# Top.net
KiCad netlist of a schematic drawn in Altium Designer
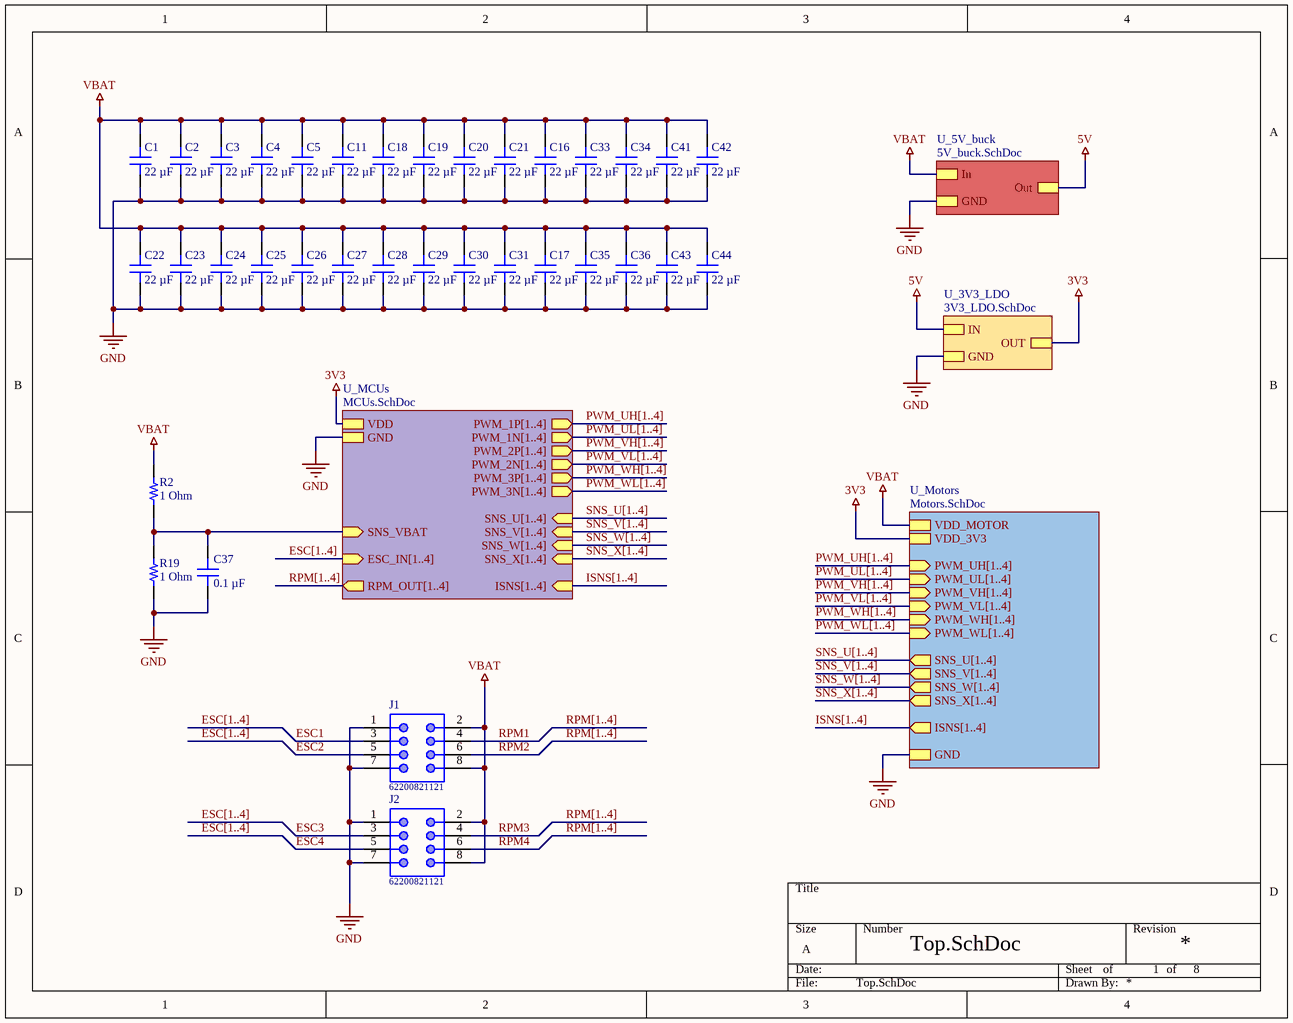
[diagram p0: Top.SchDoc]

(export (version "E")
  (design (tool "Eeschema 10.0.6"))
  (components
    (comp (ref "C1")
      (value "22 µF")
      (footprint "CAP 0805_2012")
      (description "CAP CER 22UF 25V X5R 0805")
      (fields (field (name "PART NUMBER") "CC0805MKX5R8BB226") (field (name "MANUFACTURER") "Yageo"))
      (libsource (lib "Celestial Altium Library - altium_library") (part "Capacitor"))
    )
    (comp (ref "C2")
      (value "22 µF")
      (footprint "CAP 0805_2012")
      (description "CAP CER 22UF 25V X5R 0805")
      (fields (field (name "PART NUMBER") "CC0805MKX5R8BB226") (field (name "MANUFACTURER") "Yageo"))
      (libsource (lib "Celestial Altium Library - altium_library") (part "Capacitor"))
    )
    (comp (ref "C3")
      (value "22 µF")
      (footprint "CAP 0805_2012")
      (description "CAP CER 22UF 25V X5R 0805")
      (fields (field (name "PART NUMBER") "CC0805MKX5R8BB226") (field (name "MANUFACTURER") "Yageo"))
      (libsource (lib "Celestial Altium Library - altium_library") (part "Capacitor"))
    )
    (comp (ref "C4")
      (value "22 µF")
      (footprint "CAP 0805_2012")
      (description "CAP CER 22UF 25V X5R 0805")
      (fields (field (name "PART NUMBER") "CC0805MKX5R8BB226") (field (name "MANUFACTURER") "Yageo"))
      (libsource (lib "Celestial Altium Library - altium_library") (part "Capacitor"))
    )
    (comp (ref "C5")
      (value "22 µF")
      (footprint "CAP 0805_2012")
      (description "CAP CER 22UF 25V X5R 0805")
      (fields (field (name "PART NUMBER") "CC0805MKX5R8BB226") (field (name "MANUFACTURER") "Yageo"))
      (libsource (lib "Celestial Altium Library - altium_library") (part "Capacitor"))
    )
    (comp (ref "C11")
      (value "22 µF")
      (footprint "CAP 0805_2012")
      (description "CAP CER 22UF 25V X5R 0805")
      (fields (field (name "PART NUMBER") "CC0805MKX5R8BB226") (field (name "MANUFACTURER") "Yageo"))
      (libsource (lib "Celestial Altium Library - altium_library") (part "Capacitor"))
    )
    (comp (ref "C16")
      (value "22 µF")
      (footprint "CAP 0805_2012")
      (description "CAP CER 22UF 25V X5R 0805")
      (fields (field (name "PART NUMBER") "CC0805MKX5R8BB226") (field (name "MANUFACTURER") "Yageo"))
      (libsource (lib "Celestial Altium Library - altium_library") (part "Capacitor"))
    )
    (comp (ref "C17")
      (value "22 µF")
      (footprint "CAP 0805_2012")
      (description "CAP CER 22UF 25V X5R 0805")
      (fields (field (name "PART NUMBER") "CC0805MKX5R8BB226") (field (name "MANUFACTURER") "Yageo"))
      (libsource (lib "Celestial Altium Library - altium_library") (part "Capacitor"))
    )
    (comp (ref "C18")
      (value "22 µF")
      (footprint "CAP 0805_2012")
      (description "CAP CER 22UF 25V X5R 0805")
      (fields (field (name "PART NUMBER") "CC0805MKX5R8BB226") (field (name "MANUFACTURER") "Yageo"))
      (libsource (lib "Celestial Altium Library - altium_library") (part "Capacitor"))
    )
    (comp (ref "C19")
      (value "22 µF")
      (footprint "CAP 0805_2012")
      (description "CAP CER 22UF 25V X5R 0805")
      (fields (field (name "PART NUMBER") "CC0805MKX5R8BB226") (field (name "MANUFACTURER") "Yageo"))
      (libsource (lib "Celestial Altium Library - altium_library") (part "Capacitor"))
    )
    (comp (ref "C20")
      (value "22 µF")
      (footprint "CAP 0805_2012")
      (description "CAP CER 22UF 25V X5R 0805")
      (fields (field (name "PART NUMBER") "CC0805MKX5R8BB226") (field (name "MANUFACTURER") "Yageo"))
      (libsource (lib "Celestial Altium Library - altium_library") (part "Capacitor"))
    )
    (comp (ref "C21")
      (value "22 µF")
      (footprint "CAP 0805_2012")
      (description "CAP CER 22UF 25V X5R 0805")
      (fields (field (name "PART NUMBER") "CC0805MKX5R8BB226") (field (name "MANUFACTURER") "Yageo"))
      (libsource (lib "Celestial Altium Library - altium_library") (part "Capacitor"))
    )
    (comp (ref "C22")
      (value "22 µF")
      (footprint "CAP 0805_2012")
      (description "CAP CER 22UF 25V X5R 0805")
      (fields (field (name "PART NUMBER") "CC0805MKX5R8BB226") (field (name "MANUFACTURER") "Yageo"))
      (libsource (lib "Celestial Altium Library - altium_library") (part "Capacitor"))
    )
    (comp (ref "C23")
      (value "22 µF")
      (footprint "CAP 0805_2012")
      (description "CAP CER 22UF 25V X5R 0805")
      (fields (field (name "PART NUMBER") "CC0805MKX5R8BB226") (field (name "MANUFACTURER") "Yageo"))
      (libsource (lib "Celestial Altium Library - altium_library") (part "Capacitor"))
    )
    (comp (ref "C24")
      (value "22 µF")
      (footprint "CAP 0805_2012")
      (description "CAP CER 22UF 25V X5R 0805")
      (fields (field (name "PART NUMBER") "CC0805MKX5R8BB226") (field (name "MANUFACTURER") "Yageo"))
      (libsource (lib "Celestial Altium Library - altium_library") (part "Capacitor"))
    )
    (comp (ref "C25")
      (value "22 µF")
      (footprint "CAP 0805_2012")
      (description "CAP CER 22UF 25V X5R 0805")
      (fields (field (name "PART NUMBER") "CC0805MKX5R8BB226") (field (name "MANUFACTURER") "Yageo"))
      (libsource (lib "Celestial Altium Library - altium_library") (part "Capacitor"))
    )
    (comp (ref "C26")
      (value "22 µF")
      (footprint "CAP 0805_2012")
      (description "CAP CER 22UF 25V X5R 0805")
      (fields (field (name "PART NUMBER") "CC0805MKX5R8BB226") (field (name "MANUFACTURER") "Yageo"))
      (libsource (lib "Celestial Altium Library - altium_library") (part "Capacitor"))
    )
    (comp (ref "C27")
      (value "22 µF")
      (footprint "CAP 0805_2012")
      (description "CAP CER 22UF 25V X5R 0805")
      (fields (field (name "PART NUMBER") "CC0805MKX5R8BB226") (field (name "MANUFACTURER") "Yageo"))
      (libsource (lib "Celestial Altium Library - altium_library") (part "Capacitor"))
    )
    (comp (ref "C28")
      (value "22 µF")
      (footprint "CAP 0805_2012")
      (description "CAP CER 22UF 25V X5R 0805")
      (fields (field (name "PART NUMBER") "CC0805MKX5R8BB226") (field (name "MANUFACTURER") "Yageo"))
      (libsource (lib "Celestial Altium Library - altium_library") (part "Capacitor"))
    )
    (comp (ref "C29")
      (value "22 µF")
      (footprint "CAP 0805_2012")
      (description "CAP CER 22UF 25V X5R 0805")
      (fields (field (name "PART NUMBER") "CC0805MKX5R8BB226") (field (name "MANUFACTURER") "Yageo"))
      (libsource (lib "Celestial Altium Library - altium_library") (part "Capacitor"))
    )
    (comp (ref "C30")
      (value "22 µF")
      (footprint "CAP 0805_2012")
      (description "CAP CER 22UF 25V X5R 0805")
      (fields (field (name "PART NUMBER") "CC0805MKX5R8BB226") (field (name "MANUFACTURER") "Yageo"))
      (libsource (lib "Celestial Altium Library - altium_library") (part "Capacitor"))
    )
    (comp (ref "C31")
      (value "22 µF")
      (footprint "CAP 0805_2012")
      (description "CAP CER 22UF 25V X5R 0805")
      (fields (field (name "PART NUMBER") "CC0805MKX5R8BB226") (field (name "MANUFACTURER") "Yageo"))
      (libsource (lib "Celestial Altium Library - altium_library") (part "Capacitor"))
    )
    (comp (ref "C33")
      (value "22 µF")
      (footprint "CAP 0805_2012")
      (description "CAP CER 22UF 25V X5R 0805")
      (fields (field (name "PART NUMBER") "CC0805MKX5R8BB226") (field (name "MANUFACTURER") "Yageo"))
      (libsource (lib "Celestial Altium Library - altium_library") (part "Capacitor"))
    )
    (comp (ref "C34")
      (value "22 µF")
      (footprint "CAP 0805_2012")
      (description "CAP CER 22UF 25V X5R 0805")
      (fields (field (name "PART NUMBER") "CC0805MKX5R8BB226") (field (name "MANUFACTURER") "Yageo"))
      (libsource (lib "Celestial Altium Library - altium_library") (part "Capacitor"))
    )
    (comp (ref "C35")
      (value "22 µF")
      (footprint "CAP 0805_2012")
      (description "CAP CER 22UF 25V X5R 0805")
      (fields (field (name "PART NUMBER") "CC0805MKX5R8BB226") (field (name "MANUFACTURER") "Yageo"))
      (libsource (lib "Celestial Altium Library - altium_library") (part "Capacitor"))
    )
    (comp (ref "C36")
      (value "22 µF")
      (footprint "CAP 0805_2012")
      (description "CAP CER 22UF 25V X5R 0805")
      (fields (field (name "PART NUMBER") "CC0805MKX5R8BB226") (field (name "MANUFACTURER") "Yageo"))
      (libsource (lib "Celestial Altium Library - altium_library") (part "Capacitor"))
    )
    (comp (ref "C37")
      (value "0.1 µF")
      (footprint "CAP 0402_1005")
      (description "CAP CER 0.1UF 16V X7R 0402")
      (fields (field (name "PART NUMBER") "C0402C104K4RACAUTO") (field (name "MANUFACTURER") "KEMET"))
      (libsource (lib "Celestial Altium Library - altium_library") (part "Capacitor"))
    )
    (comp (ref "C41")
      (value "22 µF")
      (footprint "CAP 0805_2012")
      (description "CAP CER 22UF 25V X5R 0805")
      (fields (field (name "PART NUMBER") "CC0805MKX5R8BB226") (field (name "MANUFACTURER") "Yageo"))
      (libsource (lib "Celestial Altium Library - altium_library") (part "Capacitor"))
    )
    (comp (ref "C42")
      (value "22 µF")
      (footprint "CAP 0805_2012")
      (description "CAP CER 22UF 25V X5R 0805")
      (fields (field (name "PART NUMBER") "CC0805MKX5R8BB226") (field (name "MANUFACTURER") "Yageo"))
      (libsource (lib "Celestial Altium Library - altium_library") (part "Capacitor"))
    )
    (comp (ref "C43")
      (value "22 µF")
      (footprint "CAP 0805_2012")
      (description "CAP CER 22UF 25V X5R 0805")
      (fields (field (name "PART NUMBER") "CC0805MKX5R8BB226") (field (name "MANUFACTURER") "Yageo"))
      (libsource (lib "Celestial Altium Library - altium_library") (part "Capacitor"))
    )
    (comp (ref "C44")
      (value "22 µF")
      (footprint "CAP 0805_2012")
      (description "CAP CER 22UF 25V X5R 0805")
      (fields (field (name "PART NUMBER") "CC0805MKX5R8BB226") (field (name "MANUFACTURER") "Yageo"))
      (libsource (lib "Celestial Altium Library - altium_library") (part "Capacitor"))
    )
    (comp (ref "J1")
      (value "62200821121")
      (footprint "62200821121")
      (description "WR-PHD Pin Header, THT, pitch 1.27mm, Dual Row, Vertical, 8p")
      (fields (field (name "MANUFACTURER") "Wurth Elektronik"))
      (libsource (lib "Altium_WR-PHD") (part "62200821121"))
    )
    (comp (ref "J2")
      (value "62200821121")
      (footprint "62200821121")
      (description "WR-PHD Pin Header, THT, pitch 1.27mm, Dual Row, Vertical, 8p")
      (fields (field (name "MANUFACTURER") "Wurth Elektronik"))
      (libsource (lib "Altium_WR-PHD") (part "62200821121"))
    )
    (comp (ref "R2")
      (value "1 Ohm")
      (footprint "RES 0402_1005")
      (description "RES 14.3K OHM 1% 1/10W 0402")
      (fields
        (field (name "PART NUMBER") "RK73H1ETTP1432F")
        (field (name "MANUFACTURER") "KOA Speer Electronics, Inc.")
      )
      (libsource (lib "Celestial Altium Library - altium_library") (part "Resistor"))
    )
    (comp (ref "R19")
      (value "1 Ohm")
      (footprint "RES 0402_1005")
      (description "RES 14.3K OHM 1% 1/10W 0402")
      (fields
        (field (name "PART NUMBER") "RK73H1ETTP1432F")
        (field (name "MANUFACTURER") "KOA Speer Electronics, Inc.")
      )
      (libsource (lib "Celestial Altium Library - altium_library") (part "Resistor"))
    )
  )
  (nets
    (net (code "45") (name "/ESC1") (class "Default")
      (node (ref "J1") (pin "3") (pinfunction "3_3") (pintype "passive"))
    )
    (net (code "46") (name "/ESC2") (class "Default")
      (node (ref "J1") (pin "5") (pinfunction "5_5") (pintype "passive"))
    )
    (net (code "47") (name "/ESC3") (class "Default")
      (node (ref "J2") (pin "3") (pinfunction "3_3") (pintype "passive"))
    )
    (net (code "48") (name "/ESC4") (class "Default")
      (node (ref "J2") (pin "5") (pinfunction "5_5") (pintype "passive"))
    )
    (net (code "57") (name "/RPM1") (class "Default")
      (node (ref "J1") (pin "4") (pinfunction "4_4") (pintype "passive"))
    )
    (net (code "58") (name "/RPM2") (class "Default")
      (node (ref "J1") (pin "6") (pinfunction "6_6") (pintype "passive"))
    )
    (net (code "59") (name "/RPM3") (class "Default")
      (node (ref "J2") (pin "4") (pinfunction "4_4") (pintype "passive"))
    )
    (net (code "60") (name "/RPM4") (class "Default")
      (node (ref "J2") (pin "6") (pinfunction "6_6") (pintype "passive"))
    )
    (net (code "63") (name "/SNS_VBAT") (class "Default")
      (node (ref "C37") (pin "2") (pinfunction "2_2") (pintype "passive"))
      (node (ref "R19") (pin "2") (pinfunction "2_2") (pintype "passive"))
      (node (ref "R2") (pin "1") (pinfunction "1_1") (pintype "passive"))
    )
    (net (code "69") (name "GND") (class "Default")
      (node (ref "C1") (pin "1") (pinfunction "1_1") (pintype "passive"))
      (node (ref "C11") (pin "1") (pinfunction "1_1") (pintype "passive"))
      (node (ref "C16") (pin "1") (pinfunction "1_1") (pintype "passive"))
      (node (ref "C17") (pin "1") (pinfunction "1_1") (pintype "passive"))
      (node (ref "C18") (pin "1") (pinfunction "1_1") (pintype "passive"))
      (node (ref "C19") (pin "1") (pinfunction "1_1") (pintype "passive"))
      (node (ref "C2") (pin "1") (pinfunction "1_1") (pintype "passive"))
      (node (ref "C20") (pin "1") (pinfunction "1_1") (pintype "passive"))
      (node (ref "C21") (pin "1") (pinfunction "1_1") (pintype "passive"))
      (node (ref "C22") (pin "1") (pinfunction "1_1") (pintype "passive"))
      (node (ref "C23") (pin "1") (pinfunction "1_1") (pintype "passive"))
      (node (ref "C24") (pin "1") (pinfunction "1_1") (pintype "passive"))
      (node (ref "C25") (pin "1") (pinfunction "1_1") (pintype "passive"))
      (node (ref "C26") (pin "1") (pinfunction "1_1") (pintype "passive"))
      (node (ref "C27") (pin "1") (pinfunction "1_1") (pintype "passive"))
      (node (ref "C28") (pin "1") (pinfunction "1_1") (pintype "passive"))
      (node (ref "C29") (pin "1") (pinfunction "1_1") (pintype "passive"))
      (node (ref "C3") (pin "1") (pinfunction "1_1") (pintype "passive"))
      (node (ref "C30") (pin "1") (pinfunction "1_1") (pintype "passive"))
      (node (ref "C31") (pin "1") (pinfunction "1_1") (pintype "passive"))
      (node (ref "C33") (pin "1") (pinfunction "1_1") (pintype "passive"))
      (node (ref "C34") (pin "1") (pinfunction "1_1") (pintype "passive"))
      (node (ref "C35") (pin "1") (pinfunction "1_1") (pintype "passive"))
      (node (ref "C36") (pin "1") (pinfunction "1_1") (pintype "passive"))
      (node (ref "C37") (pin "1") (pinfunction "1_1") (pintype "passive"))
      (node (ref "C4") (pin "1") (pinfunction "1_1") (pintype "passive"))
      (node (ref "C41") (pin "1") (pinfunction "1_1") (pintype "passive"))
      (node (ref "C42") (pin "1") (pinfunction "1_1") (pintype "passive"))
      (node (ref "C43") (pin "1") (pinfunction "1_1") (pintype "passive"))
      (node (ref "C44") (pin "1") (pinfunction "1_1") (pintype "passive"))
      (node (ref "C5") (pin "1") (pinfunction "1_1") (pintype "passive"))
      (node (ref "J1") (pin "1") (pinfunction "1_1") (pintype "passive"))
      (node (ref "J1") (pin "7") (pinfunction "7_7") (pintype "passive"))
      (node (ref "J2") (pin "1") (pinfunction "1_1") (pintype "passive"))
      (node (ref "J2") (pin "7") (pinfunction "7_7") (pintype "passive"))
      (node (ref "R19") (pin "1") (pinfunction "1_1") (pintype "passive"))
    )
    (net (code "70") (name "VBAT") (class "Default")
      (node (ref "C1") (pin "2") (pinfunction "2_2") (pintype "passive"))
      (node (ref "C11") (pin "2") (pinfunction "2_2") (pintype "passive"))
      (node (ref "C16") (pin "2") (pinfunction "2_2") (pintype "passive"))
      (node (ref "C17") (pin "2") (pinfunction "2_2") (pintype "passive"))
      (node (ref "C18") (pin "2") (pinfunction "2_2") (pintype "passive"))
      (node (ref "C19") (pin "2") (pinfunction "2_2") (pintype "passive"))
      (node (ref "C2") (pin "2") (pinfunction "2_2") (pintype "passive"))
      (node (ref "C20") (pin "2") (pinfunction "2_2") (pintype "passive"))
      (node (ref "C21") (pin "2") (pinfunction "2_2") (pintype "passive"))
      (node (ref "C22") (pin "2") (pinfunction "2_2") (pintype "passive"))
      (node (ref "C23") (pin "2") (pinfunction "2_2") (pintype "passive"))
      (node (ref "C24") (pin "2") (pinfunction "2_2") (pintype "passive"))
      (node (ref "C25") (pin "2") (pinfunction "2_2") (pintype "passive"))
      (node (ref "C26") (pin "2") (pinfunction "2_2") (pintype "passive"))
      (node (ref "C27") (pin "2") (pinfunction "2_2") (pintype "passive"))
      (node (ref "C28") (pin "2") (pinfunction "2_2") (pintype "passive"))
      (node (ref "C29") (pin "2") (pinfunction "2_2") (pintype "passive"))
      (node (ref "C3") (pin "2") (pinfunction "2_2") (pintype "passive"))
      (node (ref "C30") (pin "2") (pinfunction "2_2") (pintype "passive"))
      (node (ref "C31") (pin "2") (pinfunction "2_2") (pintype "passive"))
      (node (ref "C33") (pin "2") (pinfunction "2_2") (pintype "passive"))
      (node (ref "C34") (pin "2") (pinfunction "2_2") (pintype "passive"))
      (node (ref "C35") (pin "2") (pinfunction "2_2") (pintype "passive"))
      (node (ref "C36") (pin "2") (pinfunction "2_2") (pintype "passive"))
      (node (ref "C4") (pin "2") (pinfunction "2_2") (pintype "passive"))
      (node (ref "C41") (pin "2") (pinfunction "2_2") (pintype "passive"))
      (node (ref "C42") (pin "2") (pinfunction "2_2") (pintype "passive"))
      (node (ref "C43") (pin "2") (pinfunction "2_2") (pintype "passive"))
      (node (ref "C44") (pin "2") (pinfunction "2_2") (pintype "passive"))
      (node (ref "C5") (pin "2") (pinfunction "2_2") (pintype "passive"))
      (node (ref "J1") (pin "2") (pinfunction "2_2") (pintype "passive"))
      (node (ref "J1") (pin "8") (pinfunction "8_8") (pintype "passive"))
      (node (ref "J2") (pin "2") (pinfunction "2_2") (pintype "passive"))
      (node (ref "J2") (pin "8") (pinfunction "8_8") (pintype "passive"))
      (node (ref "R2") (pin "2") (pinfunction "2_2") (pintype "passive"))
    )
  )
)
